# PCBROCKET.net
KiCad netlist of a schematic drawn in EAGLE
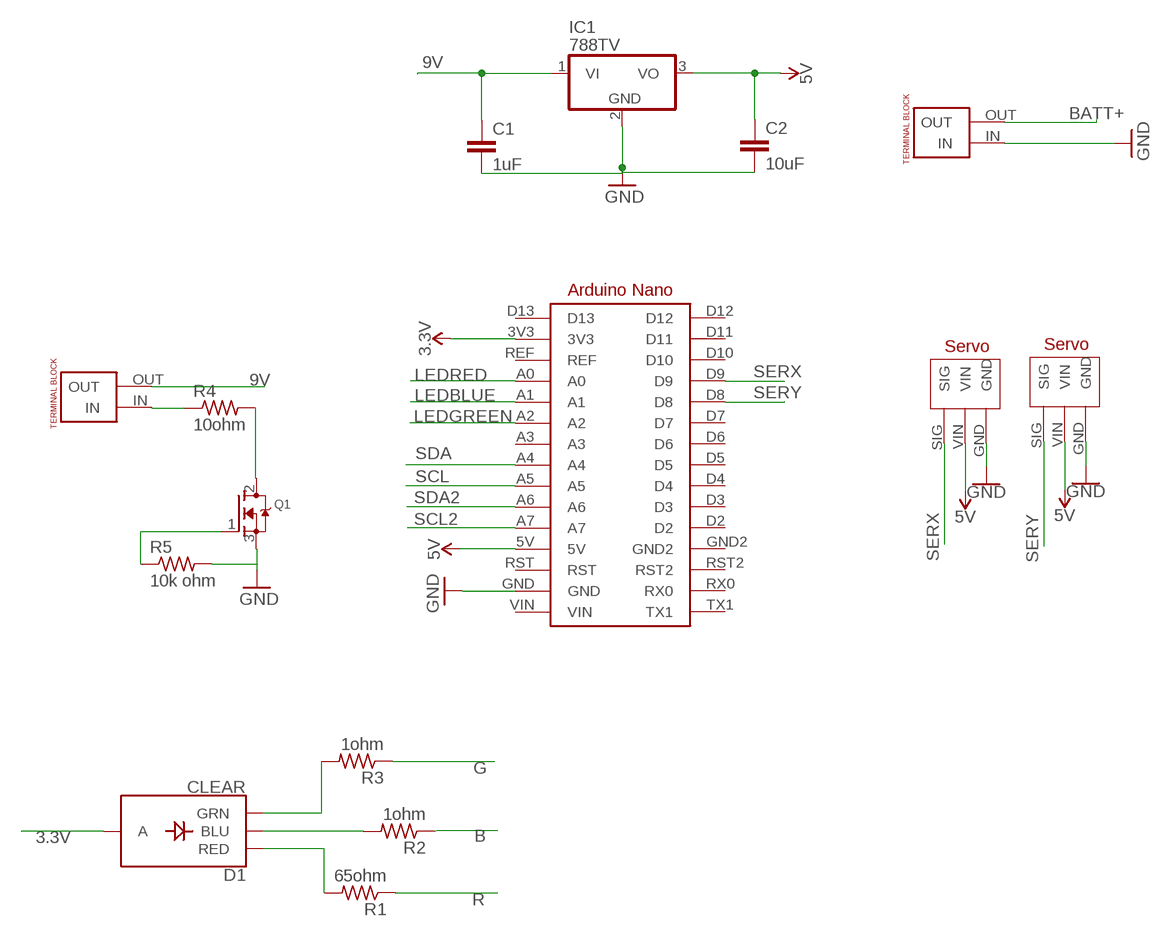
[diagram p0: schematic, sheet 1]

(export (version "E")
  (design (tool "Eeschema 10.0.6"))
  (components
    (comp (ref "C1")
      (value "1uF")
      (footprint "eagle-import:C2.5-3")
      (libsource (lib "eagle-import") (part "C2,5-3"))
    )
    (comp (ref "C2")
      (value "10uF")
      (footprint "eagle-import:C2.5-3")
      (libsource (lib "eagle-import") (part "C2,5-3"))
    )
    (comp (ref "D1")
      (value "CLEAR")
      (footprint "eagle-import:LED-RGB-THRU")
      (libsource (lib "eagle-import") (part "LED-RGB-CACLEAR"))
    )
    (comp (ref "IC1")
      (value "788TV")
      (footprint "eagle-import:TO220V")
      (libsource (lib "eagle-import") (part "78TV8"))
    )
    (comp (ref "Q1")
      (value "MOSFET-NGDS_TO220V")
      (footprint "eagle-import:TO220V")
      (libsource (lib "eagle-import") (part "MOSFET-NGDS_TO220V"))
    )
    (comp (ref "R1")
      (value "65ohm")
      (footprint "eagle-import:0204V")
      (libsource (lib "eagle-import") (part "R-US_0204/2V"))
    )
    (comp (ref "R2")
      (value "1ohm")
      (footprint "eagle-import:0204V")
      (libsource (lib "eagle-import") (part "R-US_0204/2V"))
    )
    (comp (ref "R3")
      (value "1ohm")
      (footprint "eagle-import:0204V")
      (libsource (lib "eagle-import") (part "R-US_0204/2V"))
    )
    (comp (ref "R4")
      (value "10ohm")
      (footprint "eagle-import:0204V")
      (libsource (lib "eagle-import") (part "R-US_0204/2V"))
    )
    (comp (ref "R5")
      (value "10k ohm")
      (footprint "eagle-import:0204V")
      (libsource (lib "eagle-import") (part "R-US_0204/2V"))
    )
    (comp (ref "U$1")
      (value "TERMINAL_BLOCK")
      (footprint "eagle-import:TERMINAL_BLOCK")
      (libsource (lib "eagle-import") (part "TERMINAL_BLOCK"))
    )
    (comp (ref "U$4")
      (value "ARDUINO_NANO")
      (footprint "eagle-import:ARDUINO_NANO")
      (libsource (lib "eagle-import") (part "ARDUINO_NANO"))
    )
    (comp (ref "U$5")
      (value "MG90S")
      (footprint "eagle-import:MG90S")
      (libsource (lib "eagle-import") (part "MG90S"))
    )
    (comp (ref "U$6")
      (value "MG90S")
      (footprint "eagle-import:MG90S")
      (libsource (lib "eagle-import") (part "MG90S"))
    )
    (comp (ref "U$7")
      (value "TERMINAL_BLOCK")
      (footprint "eagle-import:TERMINAL_BLOCK")
      (libsource (lib "eagle-import") (part "TERMINAL_BLOCK"))
    )
  )
  (nets
    (net (code "1") (name "/9V") (class "Default")
      (node (ref "C1") (pin "1") (pinfunction "1_1") (pintype "passive"))
      (node (ref "IC1") (pin "1") (pinfunction "VI_1") (pintype "input"))
      (node (ref "U$7") (pin "OUT") (pinfunction "OUT_OUT") (pintype "bidirectional"))
    )
    (net (code "2") (name "/B") (class "Default")
      (node (ref "R2") (pin "1") (pinfunction "1_1") (pintype "passive"))
    )
    (net (code "3") (name "/BATT+") (class "Default")
      (node (ref "U$1") (pin "OUT") (pinfunction "OUT_OUT") (pintype "bidirectional"))
    )
    (net (code "4") (name "/G") (class "Default")
      (node (ref "R3") (pin "1") (pinfunction "1_1") (pintype "passive"))
    )
    (net (code "5") (name "/LEDBLUE") (class "Default")
      (node (ref "U$4") (pin "A1") (pinfunction "A1_A1") (pintype "bidirectional"))
    )
    (net (code "6") (name "/LEDGREEN") (class "Default")
      (node (ref "U$4") (pin "A2") (pinfunction "A2_A2") (pintype "bidirectional"))
    )
    (net (code "7") (name "/LEDRED") (class "Default")
      (node (ref "U$4") (pin "A0") (pinfunction "A0_A0") (pintype "bidirectional"))
    )
    (net (code "8") (name "/R") (class "Default")
      (node (ref "R1") (pin "1") (pinfunction "1_1") (pintype "passive"))
    )
    (net (code "9") (name "/SCL") (class "Default")
      (node (ref "U$4") (pin "A5") (pinfunction "A5_A5") (pintype "bidirectional"))
    )
    (net (code "10") (name "/SCL2") (class "Default")
      (node (ref "U$4") (pin "A7") (pinfunction "A7_A7") (pintype "bidirectional"))
    )
    (net (code "11") (name "/SDA") (class "Default")
      (node (ref "U$4") (pin "A4") (pinfunction "A4_A4") (pintype "bidirectional"))
    )
    (net (code "12") (name "/SDA2") (class "Default")
      (node (ref "U$4") (pin "A6") (pinfunction "A6_A6") (pintype "bidirectional"))
    )
    (net (code "13") (name "/SERX") (class "Default")
      (node (ref "U$4") (pin "D9") (pinfunction "D9_D9") (pintype "bidirectional"))
      (node (ref "U$5") (pin "SIG") (pinfunction "SIG_SIG") (pintype "bidirectional"))
    )
    (net (code "14") (name "/SERY") (class "Default")
      (node (ref "U$4") (pin "D8") (pinfunction "D8_D8") (pintype "bidirectional"))
      (node (ref "U$6") (pin "SIG") (pinfunction "SIG_SIG") (pintype "bidirectional"))
    )
    (net (code "15") (name "3.3V") (class "Default")
      (node (ref "D1") (pin "2") (pinfunction "A_2") (pintype "bidirectional"))
      (node (ref "U$4") (pin "3V3") (pinfunction "3V3_3V3") (pintype "bidirectional"))
    )
    (net (code "16") (name "5V") (class "Default")
      (node (ref "C2") (pin "1") (pinfunction "1_1") (pintype "passive"))
      (node (ref "IC1") (pin "3") (pinfunction "VO_3") (pintype "passive"))
      (node (ref "U$4") (pin "5V") (pinfunction "5V_5V") (pintype "bidirectional"))
      (node (ref "U$5") (pin "VIN") (pinfunction "VIN_VIN") (pintype "bidirectional"))
      (node (ref "U$6") (pin "VIN") (pinfunction "VIN_VIN") (pintype "bidirectional"))
    )
    (net (code "17") (name "GND") (class "Default")
      (node (ref "C1") (pin "2") (pinfunction "2_2") (pintype "passive"))
      (node (ref "C2") (pin "2") (pinfunction "2_2") (pintype "passive"))
      (node (ref "IC1") (pin "2") (pinfunction "GND_2") (pintype "passive"))
      (node (ref "Q1") (pin "3") (pinfunction "S_3") (pintype "bidirectional"))
      (node (ref "U$1") (pin "IN") (pinfunction "IN_IN") (pintype "bidirectional"))
      (node (ref "U$4") (pin "GND") (pinfunction "GND_GND") (pintype "bidirectional"))
      (node (ref "U$5") (pin "GND") (pinfunction "GND_GND") (pintype "bidirectional"))
      (node (ref "U$6") (pin "GND") (pinfunction "GND_GND") (pintype "bidirectional"))
    )
    (net (code "18") (name "Net-(D1-BLU)") (class "Default")
      (node (ref "D1") (pin "4") (pinfunction "BLU_4") (pintype "bidirectional"))
      (node (ref "R2") (pin "2") (pinfunction "2_2") (pintype "passive"))
    )
    (net (code "19") (name "Net-(D1-GRN)") (class "Default")
      (node (ref "D1") (pin "3") (pinfunction "GRN_3") (pintype "bidirectional"))
      (node (ref "R3") (pin "2") (pinfunction "2_2") (pintype "passive"))
    )
    (net (code "20") (name "Net-(D1-RED)") (class "Default")
      (node (ref "D1") (pin "1") (pinfunction "RED_1") (pintype "bidirectional"))
      (node (ref "R1") (pin "2") (pinfunction "2_2") (pintype "passive"))
    )
    (net (code "21") (name "Net-(Q1-D)") (class "Default")
      (node (ref "Q1") (pin "2") (pinfunction "D_2") (pintype "bidirectional"))
      (node (ref "R4") (pin "2") (pinfunction "2_2") (pintype "passive"))
    )
    (net (code "22") (name "Net-(Q1-G)") (class "Default")
      (node (ref "Q1") (pin "1") (pinfunction "G_1") (pintype "bidirectional"))
      (node (ref "R5") (pin "1") (pinfunction "1_1") (pintype "passive"))
    )
    (net (code "23") (name "Net-(R4-Pad1)") (class "Default")
      (node (ref "R4") (pin "1") (pinfunction "1_1") (pintype "passive"))
      (node (ref "U$7") (pin "IN") (pinfunction "IN_IN") (pintype "bidirectional"))
    )
    (net (code "24") (name "unconnected-(R5-Pad2)") (class "Default")
      (node (ref "R5") (pin "2") (pinfunction "2_2") (pintype "passive"))
    )
    (net (code "25") (name "unconnected-(U$4-PadA3)") (class "Default")
      (node (ref "U$4") (pin "A3") (pinfunction "A3_A3") (pintype "bidirectional"))
    )
    (net (code "26") (name "unconnected-(U$4-PadD2)") (class "Default")
      (node (ref "U$4") (pin "D2") (pinfunction "D2_D2") (pintype "bidirectional"))
    )
    (net (code "27") (name "unconnected-(U$4-PadD3)") (class "Default")
      (node (ref "U$4") (pin "D3") (pinfunction "D3_D3") (pintype "bidirectional"))
    )
    (net (code "28") (name "unconnected-(U$4-PadD4)") (class "Default")
      (node (ref "U$4") (pin "D4") (pinfunction "D4_D4") (pintype "bidirectional"))
    )
    (net (code "29") (name "unconnected-(U$4-PadD5)") (class "Default")
      (node (ref "U$4") (pin "D5") (pinfunction "D5_D5") (pintype "bidirectional"))
    )
    (net (code "30") (name "unconnected-(U$4-PadD6)") (class "Default")
      (node (ref "U$4") (pin "D6") (pinfunction "D6_D6") (pintype "bidirectional"))
    )
    (net (code "31") (name "unconnected-(U$4-PadD7)") (class "Default")
      (node (ref "U$4") (pin "D7") (pinfunction "D7_D7") (pintype "bidirectional"))
    )
    (net (code "32") (name "unconnected-(U$4-PadD10)") (class "Default")
      (node (ref "U$4") (pin "D10") (pinfunction "D10_D10") (pintype "bidirectional"))
    )
    (net (code "33") (name "unconnected-(U$4-PadD11)") (class "Default")
      (node (ref "U$4") (pin "D11") (pinfunction "D11_D11") (pintype "bidirectional"))
    )
    (net (code "34") (name "unconnected-(U$4-PadD12)") (class "Default")
      (node (ref "U$4") (pin "D12") (pinfunction "D12_D12") (pintype "bidirectional"))
    )
    (net (code "35") (name "unconnected-(U$4-PadD13)") (class "Default")
      (node (ref "U$4") (pin "D13") (pinfunction "D13_D13") (pintype "bidirectional"))
    )
    (net (code "36") (name "unconnected-(U$4-PadGND2)") (class "Default")
      (node (ref "U$4") (pin "GND2") (pinfunction "GND2_GND2") (pintype "bidirectional"))
    )
    (net (code "37") (name "unconnected-(U$4-PadREF)") (class "Default")
      (node (ref "U$4") (pin "REF") (pinfunction "REF_REF") (pintype "bidirectional"))
    )
    (net (code "38") (name "unconnected-(U$4-PadRST)") (class "Default")
      (node (ref "U$4") (pin "RST") (pinfunction "RST_RST") (pintype "bidirectional"))
    )
    (net (code "39") (name "unconnected-(U$4-PadRST2)") (class "Default")
      (node (ref "U$4") (pin "RST2") (pinfunction "RST2_RST2") (pintype "bidirectional"))
    )
    (net (code "40") (name "unconnected-(U$4-PadRX0)") (class "Default")
      (node (ref "U$4") (pin "RX0") (pinfunction "RX0_RX0") (pintype "bidirectional"))
    )
    (net (code "41") (name "unconnected-(U$4-PadTX1)") (class "Default")
      (node (ref "U$4") (pin "TX1") (pinfunction "TX1_TX1") (pintype "bidirectional"))
    )
    (net (code "42") (name "unconnected-(U$4-PadVIN)") (class "Default")
      (node (ref "U$4") (pin "VIN") (pinfunction "VIN_VIN") (pintype "bidirectional"))
    )
  )
)
